# Meccano.net
KiCad netlist of a schematic drawn in EAGLE
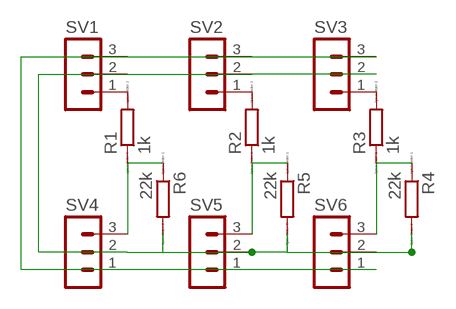
[diagram p0: schematic, sheet 1]

(export (version "E")
  (design (tool "Eeschema 10.0.6"))
  (components
    (comp (ref "R1")
      (value "1k")
      (footprint "eagle-import:0204_7")
      (libsource (lib "eagle-import") (part "R0204/7"))
    )
    (comp (ref "R2")
      (value "1k")
      (footprint "eagle-import:0204_7")
      (libsource (lib "eagle-import") (part "R0204/7"))
    )
    (comp (ref "R3")
      (value "1k")
      (footprint "eagle-import:0204_7")
      (libsource (lib "eagle-import") (part "R0204/7"))
    )
    (comp (ref "R4")
      (value "22k")
      (footprint "eagle-import:0204_7")
      (libsource (lib "eagle-import") (part "R0204/7"))
    )
    (comp (ref "R5")
      (value "22k")
      (footprint "eagle-import:0204_7")
      (libsource (lib "eagle-import") (part "R0204/7"))
    )
    (comp (ref "R6")
      (value "22k")
      (footprint "eagle-import:0204_7")
      (libsource (lib "eagle-import") (part "R0204/7"))
    )
    (comp (ref "SV1")
      (value "MA03-1")
      (footprint "eagle-import:MA03-1")
      (libsource (lib "eagle-import") (part "MA03-1"))
    )
    (comp (ref "SV2")
      (value "MA03-1")
      (footprint "eagle-import:MA03-1")
      (libsource (lib "eagle-import") (part "MA03-1"))
    )
    (comp (ref "SV3")
      (value "MA03-1")
      (footprint "eagle-import:MA03-1")
      (libsource (lib "eagle-import") (part "MA03-1"))
    )
    (comp (ref "SV4")
      (value "MA03-1")
      (footprint "eagle-import:MA03-1")
      (libsource (lib "eagle-import") (part "MA03-1"))
    )
    (comp (ref "SV5")
      (value "MA03-1")
      (footprint "eagle-import:MA03-1")
      (libsource (lib "eagle-import") (part "MA03-1"))
    )
    (comp (ref "SV6")
      (value "MA03-1")
      (footprint "eagle-import:MA03-1")
      (libsource (lib "eagle-import") (part "MA03-1"))
    )
  )
  (nets
    (net (code "1") (name "Net-(R1-Pad1)") (class "Default")
      (node (ref "R1") (pin "1") (pinfunction "1_1") (pintype "passive"))
      (node (ref "R6") (pin "1") (pinfunction "1_1") (pintype "passive"))
      (node (ref "SV4") (pin "3") (pinfunction "3_3") (pintype "passive"))
    )
    (net (code "2") (name "Net-(R1-Pad2)") (class "Default")
      (node (ref "R1") (pin "2") (pinfunction "2_2") (pintype "passive"))
      (node (ref "SV1") (pin "1") (pinfunction "1_1") (pintype "passive"))
    )
    (net (code "3") (name "Net-(R2-Pad1)") (class "Default")
      (node (ref "R2") (pin "1") (pinfunction "1_1") (pintype "passive"))
      (node (ref "R5") (pin "1") (pinfunction "1_1") (pintype "passive"))
      (node (ref "SV5") (pin "3") (pinfunction "3_3") (pintype "passive"))
    )
    (net (code "4") (name "Net-(R2-Pad2)") (class "Default")
      (node (ref "R2") (pin "2") (pinfunction "2_2") (pintype "passive"))
      (node (ref "SV2") (pin "1") (pinfunction "1_1") (pintype "passive"))
    )
    (net (code "5") (name "Net-(R3-Pad1)") (class "Default")
      (node (ref "R3") (pin "1") (pinfunction "1_1") (pintype "passive"))
      (node (ref "R4") (pin "1") (pinfunction "1_1") (pintype "passive"))
      (node (ref "SV6") (pin "3") (pinfunction "3_3") (pintype "passive"))
    )
    (net (code "6") (name "Net-(R3-Pad2)") (class "Default")
      (node (ref "R3") (pin "2") (pinfunction "2_2") (pintype "passive"))
      (node (ref "SV3") (pin "1") (pinfunction "1_1") (pintype "passive"))
    )
    (net (code "7") (name "Net-(R4-Pad2)") (class "Default")
      (node (ref "R4") (pin "2") (pinfunction "2_2") (pintype "passive"))
      (node (ref "R5") (pin "2") (pinfunction "2_2") (pintype "passive"))
      (node (ref "R6") (pin "2") (pinfunction "2_2") (pintype "passive"))
      (node (ref "SV1") (pin "2") (pinfunction "2_2") (pintype "passive"))
      (node (ref "SV2") (pin "2") (pinfunction "2_2") (pintype "passive"))
      (node (ref "SV3") (pin "2") (pinfunction "2_2") (pintype "passive"))
      (node (ref "SV4") (pin "2") (pinfunction "2_2") (pintype "passive"))
      (node (ref "SV5") (pin "2") (pinfunction "2_2") (pintype "passive"))
      (node (ref "SV6") (pin "2") (pinfunction "2_2") (pintype "passive"))
    )
    (net (code "8") (name "Net-(SV1-Pad3)") (class "Default")
      (node (ref "SV1") (pin "3") (pinfunction "3_3") (pintype "passive"))
      (node (ref "SV2") (pin "3") (pinfunction "3_3") (pintype "passive"))
      (node (ref "SV3") (pin "3") (pinfunction "3_3") (pintype "passive"))
      (node (ref "SV4") (pin "1") (pinfunction "1_1") (pintype "passive"))
      (node (ref "SV5") (pin "1") (pinfunction "1_1") (pintype "passive"))
      (node (ref "SV6") (pin "1") (pinfunction "1_1") (pintype "passive"))
    )
  )
)
